# Blo_Pen.net
KiCad netlist of a schematic drawn in EAGLE
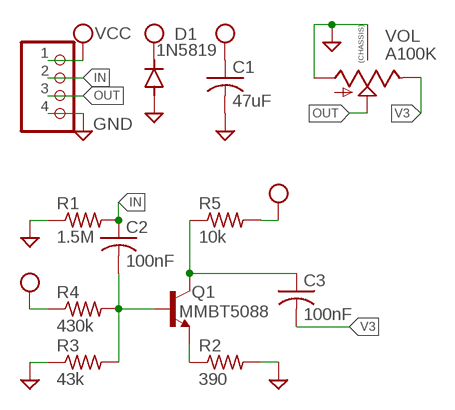
[diagram p0: schematic, sheet 1]

(export (version "E")
  (design (tool "Eeschema 10.0.6"))
  (components
    (comp (ref "C1")
      (value "47uF")
      (footprint "eagle-import:C1210")
      (libsource (lib "eagle-import") (part "rcl_334_C-USC1210"))
    )
    (comp (ref "C2")
      (value "100nF")
      (footprint "eagle-import:C0603")
      (libsource (lib "eagle-import") (part "C-USC0603"))
    )
    (comp (ref "C3")
      (value "100nF")
      (footprint "eagle-import:C0603")
      (libsource (lib "eagle-import") (part "C-USC0603"))
    )
    (comp (ref "D1")
      (value "1N5819")
      (footprint "eagle-import:SOD123")
      (libsource (lib "eagle-import") (part "DIODE-SOD123"))
    )
    (comp (ref "JP1")
      (value "PINHD-1X4")
      (footprint "eagle-import:1X04")
      (libsource (lib "eagle-import") (part "PINHD-1X4"))
    )
    (comp (ref "Q1")
      (value "MMBT5088")
      (footprint "eagle-import:SOT23-BEC")
      (fields (field (name "MF") "ON Semiconductor"))
      (libsource (lib "eagle-import") (part "MMBT5088"))
    )
    (comp (ref "R1")
      (value "1.5M")
      (footprint "eagle-import:R0603")
      (libsource (lib "eagle-import") (part "R-US_R0603"))
    )
    (comp (ref "R2")
      (value "390")
      (footprint "eagle-import:R0603")
      (libsource (lib "eagle-import") (part "R-US_R0603"))
    )
    (comp (ref "R3")
      (value "43k")
      (footprint "eagle-import:R0603")
      (libsource (lib "eagle-import") (part "R-US_R0603"))
    )
    (comp (ref "R4")
      (value "430k")
      (footprint "eagle-import:R0603")
      (libsource (lib "eagle-import") (part "R-US_R0603"))
    )
    (comp (ref "R5")
      (value "10k")
      (footprint "eagle-import:R0603")
      (libsource (lib "eagle-import") (part "R-US_R0603"))
    )
    (comp (ref "VOL")
      (value "A100K")
      (footprint "eagle-import:9MM_SNAP-IN_POT")
      (libsource (lib "eagle-import") (part "9MM_SNAP-IN_POT_CHASSIS"))
    )
  )
  (nets
    (net (code "1") (name "GND") (class "Default")
      (node (ref "C1") (pin "2") (pinfunction "2_2") (pintype "passive"))
      (node (ref "D1") (pin "A") (pinfunction "A_A") (pintype "passive"))
      (node (ref "JP1") (pin "4") (pinfunction "4_4") (pintype "passive"))
      (node (ref "R1") (pin "1") (pinfunction "1_1") (pintype "passive"))
      (node (ref "R2") (pin "2") (pinfunction "2_2") (pintype "passive"))
      (node (ref "R3") (pin "1") (pinfunction "1_1") (pintype "passive"))
      (node (ref "VOL") (pin "1") (pinfunction "A_1") (pintype "passive"))
      (node (ref "VOL") (pin "CHASSIS1") (pinfunction "P$1_CHASSIS1") (pintype "passive"))
      (node (ref "VOL") (pin "CHASSIS2") (pinfunction "P$1_CHASSIS2") (pintype "passive"))
    )
    (net (code "2") (name "IN") (class "Default")
      (node (ref "C2") (pin "1") (pinfunction "1_1") (pintype "passive"))
      (node (ref "JP1") (pin "2") (pinfunction "2_2") (pintype "passive"))
      (node (ref "R1") (pin "2") (pinfunction "2_2") (pintype "passive"))
    )
    (net (code "3") (name "Net-(C2-Pad2)") (class "Default")
      (node (ref "C2") (pin "2") (pinfunction "2_2") (pintype "passive"))
      (node (ref "Q1") (pin "B") (pinfunction "B_B") (pintype "passive"))
      (node (ref "R3") (pin "2") (pinfunction "2_2") (pintype "passive"))
      (node (ref "R4") (pin "2") (pinfunction "2_2") (pintype "passive"))
    )
    (net (code "4") (name "Net-(C3-Pad1)") (class "Default")
      (node (ref "C3") (pin "1") (pinfunction "1_1") (pintype "passive"))
      (node (ref "Q1") (pin "C") (pinfunction "C_C") (pintype "passive"))
      (node (ref "R5") (pin "1") (pinfunction "1_1") (pintype "passive"))
    )
    (net (code "5") (name "Net-(Q1-PadE)") (class "Default")
      (node (ref "Q1") (pin "E") (pinfunction "E_E") (pintype "passive"))
      (node (ref "R2") (pin "1") (pinfunction "1_1") (pintype "passive"))
    )
    (net (code "6") (name "OUT") (class "Default")
      (node (ref "JP1") (pin "3") (pinfunction "3_3") (pintype "passive"))
      (node (ref "VOL") (pin "2") (pinfunction "S_2") (pintype "passive"))
    )
    (net (code "7") (name "V3") (class "Default")
      (node (ref "C3") (pin "2") (pinfunction "2_2") (pintype "passive"))
      (node (ref "VOL") (pin "3") (pinfunction "E_3") (pintype "passive"))
    )
    (net (code "8") (name "VCC") (class "Default")
      (node (ref "C1") (pin "1") (pinfunction "1_1") (pintype "passive"))
      (node (ref "D1") (pin "C") (pinfunction "C_C") (pintype "passive"))
      (node (ref "JP1") (pin "1") (pinfunction "1_1") (pintype "passive"))
      (node (ref "R4") (pin "1") (pinfunction "1_1") (pintype "passive"))
      (node (ref "R5") (pin "2") (pinfunction "2_2") (pintype "passive"))
    )
  )
)
